# LaunchPad_TargetDevice.net
KiCad netlist of a schematic drawn in Altium Designer
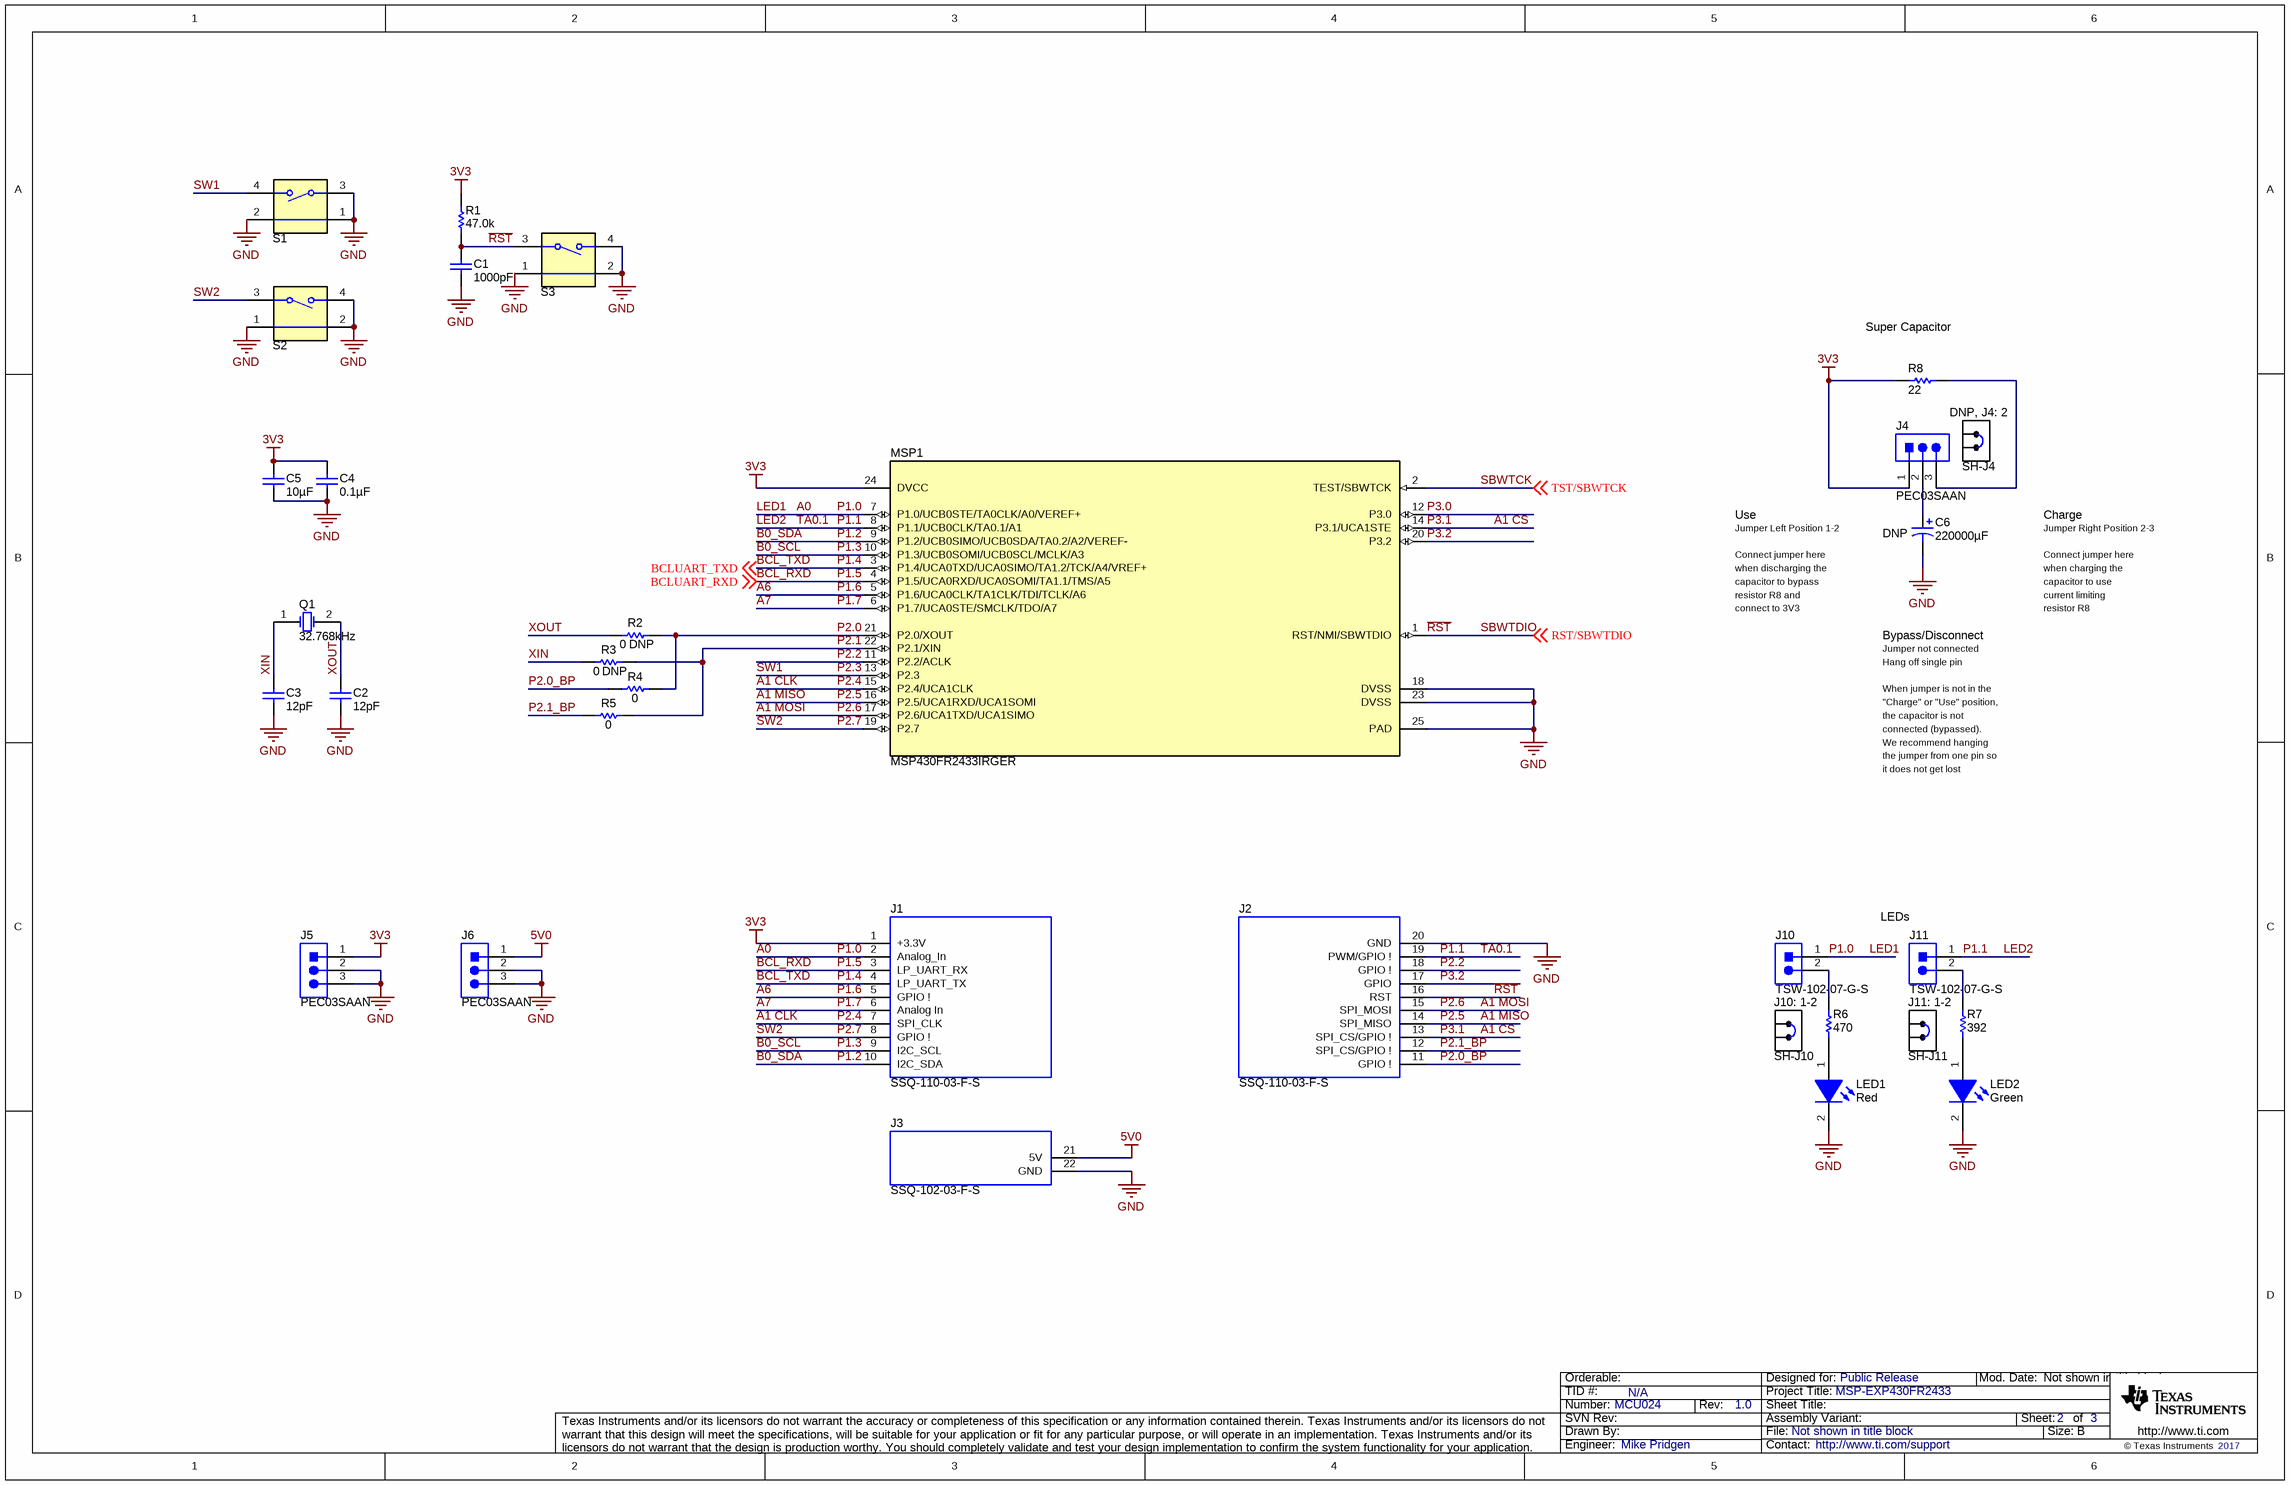
[diagram p0: LaunchPad_TargetDevice.SchDoc]

(export (version "E")
  (design (tool "Eeschema 10.0.6"))
  (components
    (comp (ref "C1")
      (value "GRM155R71H102KA01D")
      (footprint "0402")
      (description "CAP, CERM, 1000 pF, 50 V, +/- 10%, X7R, 0402")
      (fields
        (field (name "VALUEDISPLAYED") "1000pF")
        (field (name "MANUFACTURER") "MuRata")
        (field (name "PUBLISHER") "Texas Instruments")
      )
      (libsource (lib "Capacitor_Ceramic") (part "GRM155R71H102KA01D"))
    )
    (comp (ref "C2")
      (value "GRM1555C1E120JA01D")
      (footprint "0402")
      (description "CAP, CERM, 12 pF, 25 V, +/- 5%, C0G/NP0, 0402")
      (fields
        (field (name "VALUEDISPLAYED") "12pF")
        (field (name "MANUFACTURER") "MuRata")
        (field (name "PUBLISHER") "Texas Instruments")
      )
      (libsource (lib "Capacitor_Ceramic") (part "GRM1555C1E120JA01D"))
    )
    (comp (ref "C3")
      (value "GRM1555C1E120JA01D")
      (footprint "0402")
      (description "CAP, CERM, 12 pF, 25 V, +/- 5%, C0G/NP0, 0402")
      (fields
        (field (name "VALUEDISPLAYED") "12pF")
        (field (name "MANUFACTURER") "MuRata")
        (field (name "PUBLISHER") "Texas Instruments")
      )
      (libsource (lib "Capacitor_Ceramic") (part "GRM1555C1E120JA01D"))
    )
    (comp (ref "C4")
      (value "GRM155R61H104ME14D")
      (footprint "0402")
      (description "CAP, CERM, 0.1 µF, 50 V, +/- 20%, X5R, 0402")
      (fields
        (field (name "VALUEDISPLAYED") "0.1µF")
        (field (name "MANUFACTURER") "MuRata")
        (field (name "PUBLISHER") "Texas Instruments")
      )
      (libsource (lib "Capacitor_Ceramic") (part "GRM155R61H104ME14D"))
    )
    (comp (ref "C5")
      (value "GRM188R60J106ME84")
      (footprint "0603")
      (description "CAP, CERM, 10 µF, 6.3 V, +/- 20%, X5R, 0603")
      (fields
        (field (name "VALUEDISPLAYED") "10µF")
        (field (name "MANUFACTURER") "MuRata")
        (field (name "PUBLISHER") "Texas Instruments")
      )
      (libsource (lib "Capacitor_Ceramic") (part "GRM188R60J106ME84"))
    )
    (comp (ref "C6")
      (value "EEC-S0HD224H")
      (footprint "SD_1050x600")
      (description "CAP, Electric Double Layer, 220000 µF, 5.5 V, +80/-20%, TH")
      (fields
        (field (name "VALUEDISPLAYED") "220000µF")
        (field (name "MANUFACTURER") "Panasonic")
        (field (name "NOTE") "DNP")
        (field (name "PUBLISHER") "Texas Instruments")
      )
      (libsource (lib "Capacitor_Other") (part "EEC-S0HD224H"))
    )
    (comp (ref "J1")
      (value "SSQ-110-03-F-S")
      (footprint "BoosterPack_20pin_J1")
      (description "Receptacle, 2.54mm, 10x1, Gold, TH")
      (fields
        (field (name "MANUFACTURER") "Samtec")
        (field (name "ALTERNATE PARTNUMBER") "SSHQ-110-S-08-G-LF")
        (field (name "SYMBOLCREATOR") "a0412235")
        (field (name "PUBLISHER") "Texas Instruments")
      )
      (libsource (lib "Hardware") (part "BoosterPack_20pin_J1"))
    )
    (comp (ref "J2")
      (value "SSQ-110-03-F-S")
      (footprint "BoosterPack_20pin_J2")
      (description "Receptacle, 2.54mm, 10x1, Gold, TH")
      (fields
        (field (name "MANUFACTURER") "Samtec")
        (field (name "ALTERNATE PARTNUMBER") "SSHQ-110-S-08-G-LF")
        (field (name "SYMBOLCREATOR") "a0412235")
        (field (name "PUBLISHER") "Texas Instruments")
      )
      (libsource (lib "Hardware") (part "BoosterPack_20pin_J2"))
    )
    (comp (ref "J3")
      (value "SSQ-102-03-F-S")
      (footprint "BoosterPack_20pin_J3")
      (description "Receptacle, 2.54mm, 2x1, Gold, TH")
      (fields
        (field (name "MANUFACTURER") "Samtec")
        (field (name "SYMBOLCREATOR") "a0412235")
        (field (name "PUBLISHER") "Texas Instruments")
      )
      (libsource (lib "Hardware") (part "BoosterPack_20pin_J3"))
    )
    (comp (ref "J4")
      (value "PEC03SAAN")
      (footprint "CONN_PEC03SAAN")
      (description "Header, 100mil, 3x1, Tin, TH")
      (fields
        (field (name "MANUFACTURER") "Sullins Connector Solutions")
        (field (name "SYMBOLCREATOR") "a0412235")
        (field (name "PUBLISHER") "Texas Instruments")
      )
      (libsource (lib "Connectors_Sullins") (part "PEC03SAAN"))
    )
    (comp (ref "J5")
      (value "PEC03SAAN")
      (footprint "PEC03SAAN_Launchpad_3V3")
      (description "Header, 100mil, 3x1, Tin, TH")
      (fields
        (field (name "MANUFACTURER") "Sullins Connector Solutions")
        (field (name "SYMBOLCREATOR") "a0799628")
        (field (name "PUBLISHER") "Texas Instruments")
      )
      (libsource (lib "") (part "PEC03SAAN_1"))
    )
    (comp (ref "J6")
      (value "PEC03SAAN")
      (footprint "PEC03SAAN_Launchpad_5V0")
      (description "Header, 100mil, 3x1, Tin, TH")
      (fields
        (field (name "MANUFACTURER") "Sullins Connector Solutions")
        (field (name "SYMBOLCREATOR") "a0799628")
        (field (name "PUBLISHER") "Texas Instruments")
      )
      (libsource (lib "") (part "PEC03SAAN_1"))
    )
    (comp (ref "J10")
      (value "TSW-102-07-G-S")
      (footprint "TSW-102-07-G-S")
      (description "Header, 100mil, 2x1, Gold, TH")
      (fields
        (field (name "MANUFACTURER") "Samtec")
        (field (name "SYMBOLCREATOR") "a0412235")
        (field (name "PUBLISHER") "Texas Instruments")
      )
      (libsource (lib "Connectors_Samtec") (part "TSW-102-07-G-S"))
    )
    (comp (ref "J11")
      (value "TSW-102-07-G-S")
      (footprint "TSW-102-07-G-S")
      (description "Header, 100mil, 2x1, Gold, TH")
      (fields
        (field (name "MANUFACTURER") "Samtec")
        (field (name "SYMBOLCREATOR") "a0412235")
        (field (name "PUBLISHER") "Texas Instruments")
      )
      (libsource (lib "Connectors_Samtec") (part "TSW-102-07-G-S"))
    )
    (comp (ref "LED1")
      (value "Red")
      (footprint "LED_LTST-C190_Red")
      (description "LED, Red, SMD")
      (fields
        (field (name "PARTNUMBER") "LTST-C190CKT")
        (field (name "MANUFACTURER") "Lite-On")
        (field (name "PUBLISHER") "Texas Instruments")
      )
      (libsource (lib "LED") (part "LTST-C190CKT"))
    )
    (comp (ref "LED2")
      (value "Green")
      (footprint "LED_LTST-C190")
      (description "LED, Green, SMD")
      (fields
        (field (name "PARTNUMBER") "LTST-C190GKT")
        (field (name "MANUFACTURER") "Lite-On")
        (field (name "PUBLISHER") "Texas Instruments")
      )
      (libsource (lib "LED") (part "LTST-C190GKT"))
    )
    (comp (ref "MSP1")
      (value "MSP430FR2433IRGER")
      (footprint "RGE0024H")
      (fields
        (field (name "ALTERNATE PARTNUMBER") "MSP430FR2433IRGET")
        (field (name "MANUFACTURER") "Texas Instruments")
        (field (name "SYMBOLCREATOR") "Altium")
        (field (name "PUBLISHER") "Texas Instruments")
      )
      (libsource (lib "TI_Pre_Release1") (part "MSP430FR2433IRGER"))
    )
    (comp (ref "Q1")
      (value "X1A0001410014")
      (footprint "Epson_FC-135")
      (description "Crystal, 32.768 KHz, 12.5 pF, SMD")
      (fields
        (field (name "FREQUENCY") "32.768kHz")
        (field (name "MANUFACTURER") "Epson")
        (field (name "SYMBOLCREATOR") "a0412235")
        (field (name "PUBLISHER") "Texas Instruments")
      )
      (libsource (lib "Oscillators") (part "X1A0001410014"))
    )
    (comp (ref "R1")
      (value "RC0402FR-0747KL")
      (footprint "0402")
      (description "RES, 47.0 k, 1%, 0.0625 W, 0402")
      (fields
        (field (name "VALUEDISPLAYED") "47.0k")
        (field (name "MANUFACTURER") "Yageo America")
        (field (name "PUBLISHER") "Texas Instruments")
      )
      (libsource (lib "Resistor_0402") (part "RC0402FR-0747KL"))
    )
    (comp (ref "R2")
      (value "CRCW06030000Z0EA")
      (footprint "0603")
      (description "RES, 0, 5%, 0.1 W, 0603")
      (fields
        (field (name "VALUEDISPLAYED") "0")
        (field (name "MANUFACTURER") "Vishay-Dale")
        (field (name "NOTE") "DNP")
        (field (name "PUBLISHER") "Texas Instruments")
      )
      (libsource (lib "Resistor_0603") (part "CRCW06030000Z0EA"))
    )
    (comp (ref "R3")
      (value "CRCW06030000Z0EA")
      (footprint "0603")
      (description "RES, 0, 5%, 0.1 W, 0603")
      (fields
        (field (name "VALUEDISPLAYED") "0")
        (field (name "MANUFACTURER") "Vishay-Dale")
        (field (name "NOTE") "DNP")
        (field (name "PUBLISHER") "Texas Instruments")
      )
      (libsource (lib "Resistor_0603") (part "CRCW06030000Z0EA"))
    )
    (comp (ref "R4")
      (value "CRCW06030000Z0EA")
      (footprint "0603")
      (description "RES, 0, 5%, 0.1 W, 0603")
      (fields
        (field (name "VALUEDISPLAYED") "0")
        (field (name "MANUFACTURER") "Vishay-Dale")
        (field (name "PUBLISHER") "Texas Instruments")
      )
      (libsource (lib "Resistor_0603") (part "CRCW06030000Z0EA"))
    )
    (comp (ref "R5")
      (value "CRCW06030000Z0EA")
      (footprint "0603")
      (description "RES, 0, 5%, 0.1 W, 0603")
      (fields
        (field (name "VALUEDISPLAYED") "0")
        (field (name "MANUFACTURER") "Vishay-Dale")
        (field (name "PUBLISHER") "Texas Instruments")
      )
      (libsource (lib "Resistor_0603") (part "CRCW06030000Z0EA"))
    )
    (comp (ref "R6")
      (value "RC0402FR-07470RL")
      (footprint "0402")
      (description "RES, 470, 1%, 0.063 W, 0402")
      (fields
        (field (name "VALUEDISPLAYED") "470")
        (field (name "MANUFACTURER") "Yageo America")
        (field (name "PUBLISHER") "Texas Instruments")
      )
      (libsource (lib "Resistor_0402") (part "RC0402FR-07470RL"))
    )
    (comp (ref "R7")
      (value "CRCW0402392RFKED")
      (footprint "0402")
      (description "RES, 392, 1%, 0.063 W, 0402")
      (fields
        (field (name "VALUEDISPLAYED") "392")
        (field (name "MANUFACTURER") "Vishay-Dale")
        (field (name "PUBLISHER") "Texas Instruments")
      )
      (libsource (lib "Resistor_0402") (part "CRCW0402392RFKED"))
    )
    (comp (ref "R8")
      (value "CRCW120622R0JNEA")
      (footprint "1206")
      (description "RES, 22, 5%, 0.25 W, 1206")
      (fields
        (field (name "VALUEDISPLAYED") "22")
        (field (name "MANUFACTURER") "Vishay-Dale")
        (field (name "PUBLISHER") "Texas Instruments")
      )
      (libsource (lib "Resistor_1206") (part "CRCW120622R0JNEA"))
    )
    (comp (ref "S1")
      (value "1188E-1K2-V-TR")
      (footprint "SW_1188E")
      (description "Switch, SPST, 0.05 A, 12 VDC, SMD")
      (fields
        (field (name "MANUFACTURER") "Diptronics")
        (field (name "SYMBOLCREATOR") "Altium")
        (field (name "PUBLISHER") "Texas Instruments")
      )
      (libsource (lib "") (part "1188E-1K2-V-TR_1"))
    )
    (comp (ref "S2")
      (value "1188E-1K2-V-TR")
      (footprint "SW_1188E")
      (description "Switch, SPST, 0.05 A, 12 VDC, SMD")
      (fields
        (field (name "MANUFACTURER") "Diptronics")
        (field (name "SYMBOLCREATOR") "Altium")
        (field (name "PUBLISHER") "Texas Instruments")
      )
      (libsource (lib "Switches") (part "1188E-1K2-V-TR"))
    )
    (comp (ref "S3")
      (value "1188E-1K2-V-TR")
      (footprint "SW_1188E")
      (description "Switch, SPST, 0.05 A, 12 VDC, SMD")
      (fields
        (field (name "MANUFACTURER") "Diptronics")
        (field (name "SYMBOLCREATOR") "Altium")
        (field (name "PUBLISHER") "Texas Instruments")
      )
      (libsource (lib "Switches") (part "1188E-1K2-V-TR"))
    )
    (comp (ref "SH-J4")
      (value "SNT-100-BK-G")
      (footprint "SNT-100-BK-G")
      (description "Shunt, 100mil, Gold plated, Black")
      (fields
        (field (name "MANUFACTURER") "Samtec")
        (field (name "NOTE") "DNP, J4: 2")
        (field (name "ALTERNATE PARTNUMBER") "969102-0000-DA")
        (field (name "PUBLISHER") "Texas Instruments")
      )
      (libsource (lib "Hardware") (part "SNT-100-BK-G"))
    )
    (comp (ref "SH-J10")
      (value "SNT-100-BK-G")
      (footprint "SNT-100-BK-G")
      (description "Shunt, 100mil, Gold plated, Black")
      (fields
        (field (name "MANUFACTURER") "Samtec")
        (field (name "NOTE") "J10: 1-2")
        (field (name "ALTERNATE PARTNUMBER") "969102-0000-DA")
        (field (name "PUBLISHER") "Texas Instruments")
      )
      (libsource (lib "Hardware") (part "SNT-100-BK-G"))
    )
    (comp (ref "SH-J11")
      (value "SNT-100-BK-G")
      (footprint "SNT-100-BK-G")
      (description "Shunt, 100mil, Gold plated, Black")
      (fields
        (field (name "MANUFACTURER") "Samtec")
        (field (name "NOTE") "J11: 1-2")
        (field (name "ALTERNATE PARTNUMBER") "969102-0000-DA")
        (field (name "PUBLISHER") "Texas Instruments")
      )
      (libsource (lib "Hardware") (part "SNT-100-BK-G"))
    )
  )
  (nets
    (net (code "1") (name "/A0") (class "Default")
      (node (ref "J1") (pin "2") (pinfunction "Analog_In_2") (pintype "passive"))
      (node (ref "J10") (pin "1") (pinfunction "1_1") (pintype "passive"))
      (node (ref "MSP1") (pin "7") (pinfunction "P1.0/UCB0STE/TA0CLK/A0/VEREF+_7") (pintype "bidirectional"))
    )
    (net (code "2") (name "/A1 CLK") (class "Default")
      (node (ref "J1") (pin "7") (pinfunction "SPI_CLK_7") (pintype "passive"))
      (node (ref "MSP1") (pin "15") (pinfunction "P2.4/UCA1CLK_15") (pintype "bidirectional"))
    )
    (net (code "3") (name "/A1 CS") (class "Default")
      (node (ref "J2") (pin "13") (pinfunction "SPI_CS/GPIO_!_13") (pintype "passive"))
      (node (ref "MSP1") (pin "14") (pinfunction "P3.1/UCA1STE_14") (pintype "bidirectional"))
    )
    (net (code "4") (name "/A1 MISO") (class "Default")
      (node (ref "J2") (pin "14") (pinfunction "SPI_MISO_14") (pintype "passive"))
      (node (ref "MSP1") (pin "16") (pinfunction "P2.5/UCA1RXD/UCA1SOMI_16") (pintype "bidirectional"))
    )
    (net (code "5") (name "/A1 MOSI") (class "Default")
      (node (ref "J2") (pin "15") (pinfunction "SPI_MOSI_15") (pintype "passive"))
      (node (ref "MSP1") (pin "17") (pinfunction "P2.6/UCA1TXD/UCA1SIMO_17") (pintype "bidirectional"))
    )
    (net (code "6") (name "/A6") (class "Default")
      (node (ref "J1") (pin "5") (pinfunction "GPIO_!_5") (pintype "passive"))
      (node (ref "MSP1") (pin "5") (pinfunction "P1.6/UCA0CLK/TA1CLK/TDI/TCLK/A6_5") (pintype "bidirectional"))
    )
    (net (code "7") (name "/A7") (class "Default")
      (node (ref "J1") (pin "6") (pinfunction "Analog_In_6") (pintype "passive"))
      (node (ref "MSP1") (pin "6") (pinfunction "P1.7/UCA0STE/SMCLK/TDO/A7_6") (pintype "bidirectional"))
    )
    (net (code "8") (name "/B0_SCL") (class "Default")
      (node (ref "J1") (pin "9") (pinfunction "I2C_SCL_9") (pintype "passive"))
      (node (ref "MSP1") (pin "10") (pinfunction "P1.3/UCB0SOMI/UCB0SCL/MCLK/A3_10") (pintype "bidirectional"))
    )
    (net (code "9") (name "/B0_SDA") (class "Default")
      (node (ref "J1") (pin "10") (pinfunction "I2C_SDA_10") (pintype "passive"))
      (node (ref "MSP1") (pin "9") (pinfunction "P1.2/UCB0SIMO/UCB0SDA/TA0.2/A2/VEREF-_9") (pintype "bidirectional"))
    )
    (net (code "10") (name "/LED2") (class "Default")
      (node (ref "J11") (pin "1") (pinfunction "1_1") (pintype "passive"))
      (node (ref "J2") (pin "19") (pinfunction "PWM/GPIO_!_19") (pintype "passive"))
      (node (ref "MSP1") (pin "8") (pinfunction "P1.1/UCB0CLK/TA0.1/A1_8") (pintype "bidirectional"))
    )
    (net (code "11") (name "/P2.0") (class "Default")
      (node (ref "MSP1") (pin "21") (pinfunction "P2.0/XOUT_21") (pintype "bidirectional"))
      (node (ref "R2") (pin "2") (pinfunction "2_2") (pintype "passive"))
      (node (ref "R4") (pin "2") (pinfunction "2_2") (pintype "passive"))
    )
    (net (code "12") (name "/P2.0_BP") (class "Default")
      (node (ref "J2") (pin "11") (pinfunction "GPIO_!_11") (pintype "passive"))
      (node (ref "R4") (pin "1") (pinfunction "1_1") (pintype "passive"))
    )
    (net (code "13") (name "/P2.1") (class "Default")
      (node (ref "MSP1") (pin "22") (pinfunction "P2.1/XIN_22") (pintype "bidirectional"))
      (node (ref "R3") (pin "2") (pinfunction "2_2") (pintype "passive"))
      (node (ref "R5") (pin "2") (pinfunction "2_2") (pintype "passive"))
    )
    (net (code "14") (name "/P2.1_BP") (class "Default")
      (node (ref "J2") (pin "12") (pinfunction "SPI_CS/GPIO_!_12") (pintype "passive"))
      (node (ref "R5") (pin "1") (pinfunction "1_1") (pintype "passive"))
    )
    (net (code "15") (name "/P2.2") (class "Default")
      (node (ref "J2") (pin "18") (pinfunction "GPIO_!_18") (pintype "passive"))
      (node (ref "MSP1") (pin "11") (pinfunction "P2.2/ACLK_11") (pintype "bidirectional"))
    )
    (net (code "16") (name "/P2.3") (class "Default")
      (node (ref "MSP1") (pin "13") (pinfunction "P2.3_13") (pintype "bidirectional"))
      (node (ref "S1") (pin "4") (pinfunction "4_4") (pintype "passive"))
    )
    (net (code "17") (name "/P2.7") (class "Default")
      (node (ref "J1") (pin "8") (pinfunction "GPIO_!_8") (pintype "passive"))
      (node (ref "MSP1") (pin "19") (pinfunction "P2.7_19") (pintype "bidirectional"))
      (node (ref "S2") (pin "3") (pinfunction "3_3") (pintype "passive"))
    )
    (net (code "18") (name "/P3.0") (class "Default")
      (node (ref "MSP1") (pin "12") (pinfunction "P3.0_12") (pintype "bidirectional"))
    )
    (net (code "19") (name "/P3.2") (class "Default")
      (node (ref "J2") (pin "17") (pinfunction "GPIO_17") (pintype "passive"))
      (node (ref "MSP1") (pin "20") (pinfunction "P3.2_20") (pintype "bidirectional"))
    )
    (net (code "20") (name "/XIN") (class "Default")
      (node (ref "C3") (pin "1") (pinfunction "1_1") (pintype "passive"))
      (node (ref "Q1") (pin "1") (pinfunction "OSC1_1") (pintype "passive"))
      (node (ref "R3") (pin "1") (pinfunction "1_1") (pintype "passive"))
    )
    (net (code "21") (name "/XOUT") (class "Default")
      (node (ref "C2") (pin "1") (pinfunction "1_1") (pintype "passive"))
      (node (ref "Q1") (pin "2") (pinfunction "OSC2_2") (pintype "passive"))
      (node (ref "R2") (pin "1") (pinfunction "1_1") (pintype "passive"))
    )
    (net (code "22") (name "3V3") (class "Default")
      (node (ref "C4") (pin "1") (pinfunction "1_1") (pintype "passive"))
      (node (ref "C5") (pin "2") (pinfunction "2_2") (pintype "passive"))
      (node (ref "J1") (pin "1") (pinfunction "+3.3V_1") (pintype "power_in"))
      (node (ref "J4") (pin "1") (pinfunction "1_1") (pintype "passive"))
      (node (ref "J5") (pin "1") (pinfunction "1_1") (pintype "passive"))
      (node (ref "MSP1") (pin "24") (pinfunction "DVCC_24") (pintype "power_in"))
      (node (ref "R1") (pin "2") (pinfunction "2_2") (pintype "passive"))
      (node (ref "R8") (pin "1") (pinfunction "1_1") (pintype "passive"))
    )
    (net (code "23") (name "5V0") (class "Default")
      (node (ref "J3") (pin "21") (pinfunction "5V_21") (pintype "power_in"))
      (node (ref "J6") (pin "1") (pinfunction "1_1") (pintype "passive"))
    )
    (net (code "24") (name "BCLUART_RXD") (class "Default")
      (node (ref "J1") (pin "3") (pinfunction "LP_UART_RX_3") (pintype "passive"))
      (node (ref "MSP1") (pin "4") (pinfunction "P1.5/UCA0RXD/UCA0SOMI/TA1.1/TMS/A5_4") (pintype "bidirectional"))
    )
    (net (code "25") (name "BCLUART_TXD") (class "Default")
      (node (ref "J1") (pin "4") (pinfunction "LP_UART_TX_4") (pintype "passive"))
      (node (ref "MSP1") (pin "3") (pinfunction "P1.4/UCA0TXD/UCA0SIMO/TA1.2/TCK/A4/VREF+_3") (pintype "bidirectional"))
    )
    (net (code "26") (name "GND") (class "Default")
      (node (ref "C1") (pin "2") (pinfunction "2_2") (pintype "passive"))
      (node (ref "C2") (pin "2") (pinfunction "2_2") (pintype "passive"))
      (node (ref "C3") (pin "2") (pinfunction "2_2") (pintype "passive"))
      (node (ref "C4") (pin "2") (pinfunction "2_2") (pintype "passive"))
      (node (ref "C5") (pin "1") (pinfunction "1_1") (pintype "passive"))
      (node (ref "C6") (pin "2") (pinfunction "-_2") (pintype "passive"))
      (node (ref "J2") (pin "20") (pinfunction "GND_20") (pintype "power_in"))
      (node (ref "J3") (pin "22") (pinfunction "GND_22") (pintype "power_in"))
      (node (ref "J5") (pin "2") (pinfunction "2_2") (pintype "passive"))
      (node (ref "J5") (pin "3") (pinfunction "3_3") (pintype "passive"))
      (node (ref "J6") (pin "2") (pinfunction "2_2") (pintype "passive"))
      (node (ref "J6") (pin "3") (pinfunction "3_3") (pintype "passive"))
      (node (ref "LED1") (pin "2") (pinfunction "K_2") (pintype "passive"))
      (node (ref "LED2") (pin "2") (pinfunction "K_2") (pintype "passive"))
      (node (ref "MSP1") (pin "18") (pinfunction "DVSS_18") (pintype "power_in"))
      (node (ref "MSP1") (pin "23") (pinfunction "DVSS_23") (pintype "power_in"))
      (node (ref "MSP1") (pin "25") (pinfunction "PAD_25") (pintype "power_in"))
      (node (ref "S1") (pin "1") (pinfunction "1_1") (pintype "passive"))
      (node (ref "S1") (pin "2") (pinfunction "2_2") (pintype "passive"))
      (node (ref "S1") (pin "3") (pinfunction "3_3") (pintype "passive"))
      (node (ref "S2") (pin "1") (pinfunction "1_1") (pintype "passive"))
      (node (ref "S2") (pin "2") (pinfunction "2_2") (pintype "passive"))
      (node (ref "S2") (pin "4") (pinfunction "4_4") (pintype "passive"))
      (node (ref "S3") (pin "1") (pinfunction "1_1") (pintype "passive"))
      (node (ref "S3") (pin "2") (pinfunction "2_2") (pintype "passive"))
      (node (ref "S3") (pin "4") (pinfunction "4_4") (pintype "passive"))
    )
    (net (code "27") (name "Net-(C6-+)") (class "Default")
      (node (ref "C6") (pin "1") (pinfunction "+_1") (pintype "passive"))
      (node (ref "J4") (pin "2") (pinfunction "2_2") (pintype "passive"))
    )
    (net (code "28") (name "Net-(J4-Pad3)") (class "Default")
      (node (ref "J4") (pin "3") (pinfunction "3_3") (pintype "passive"))
      (node (ref "R8") (pin "2") (pinfunction "2_2") (pintype "passive"))
    )
    (net (code "29") (name "Net-(J10-Pad2)") (class "Default")
      (node (ref "J10") (pin "2") (pinfunction "2_2") (pintype "passive"))
      (node (ref "R6") (pin "2") (pinfunction "2_2") (pintype "passive"))
    )
    (net (code "30") (name "Net-(J11-Pad2)") (class "Default")
      (node (ref "J11") (pin "2") (pinfunction "2_2") (pintype "passive"))
      (node (ref "R7") (pin "2") (pinfunction "2_2") (pintype "passive"))
    )
    (net (code "31") (name "Net-(LED1-A)") (class "Default")
      (node (ref "LED1") (pin "1") (pinfunction "A_1") (pintype "passive"))
      (node (ref "R6") (pin "1") (pinfunction "1_1") (pintype "passive"))
    )
    (net (code "32") (name "Net-(LED2-A)") (class "Default")
      (node (ref "LED2") (pin "1") (pinfunction "A_1") (pintype "passive"))
      (node (ref "R7") (pin "1") (pinfunction "1_1") (pintype "passive"))
    )
    (net (code "33") (name "RST{slash}SBWTDIO") (class "Default")
      (node (ref "C1") (pin "1") (pinfunction "1_1") (pintype "passive"))
      (node (ref "J2") (pin "16") (pinfunction "RST_16") (pintype "passive"))
      (node (ref "MSP1") (pin "1") (pinfunction "RST/NMI/SBWTDIO_1") (pintype "bidirectional"))
      (node (ref "R1") (pin "1") (pinfunction "1_1") (pintype "passive"))
      (node (ref "S3") (pin "3") (pinfunction "3_3") (pintype "passive"))
    )
    (net (code "34") (name "TST{slash}SBWTCK") (class "Default")
      (node (ref "MSP1") (pin "2") (pinfunction "TEST/SBWTCK_2") (pintype "input"))
    )
  )
)
